# LNA.net
KiCad netlist of a schematic drawn in Altium Designer
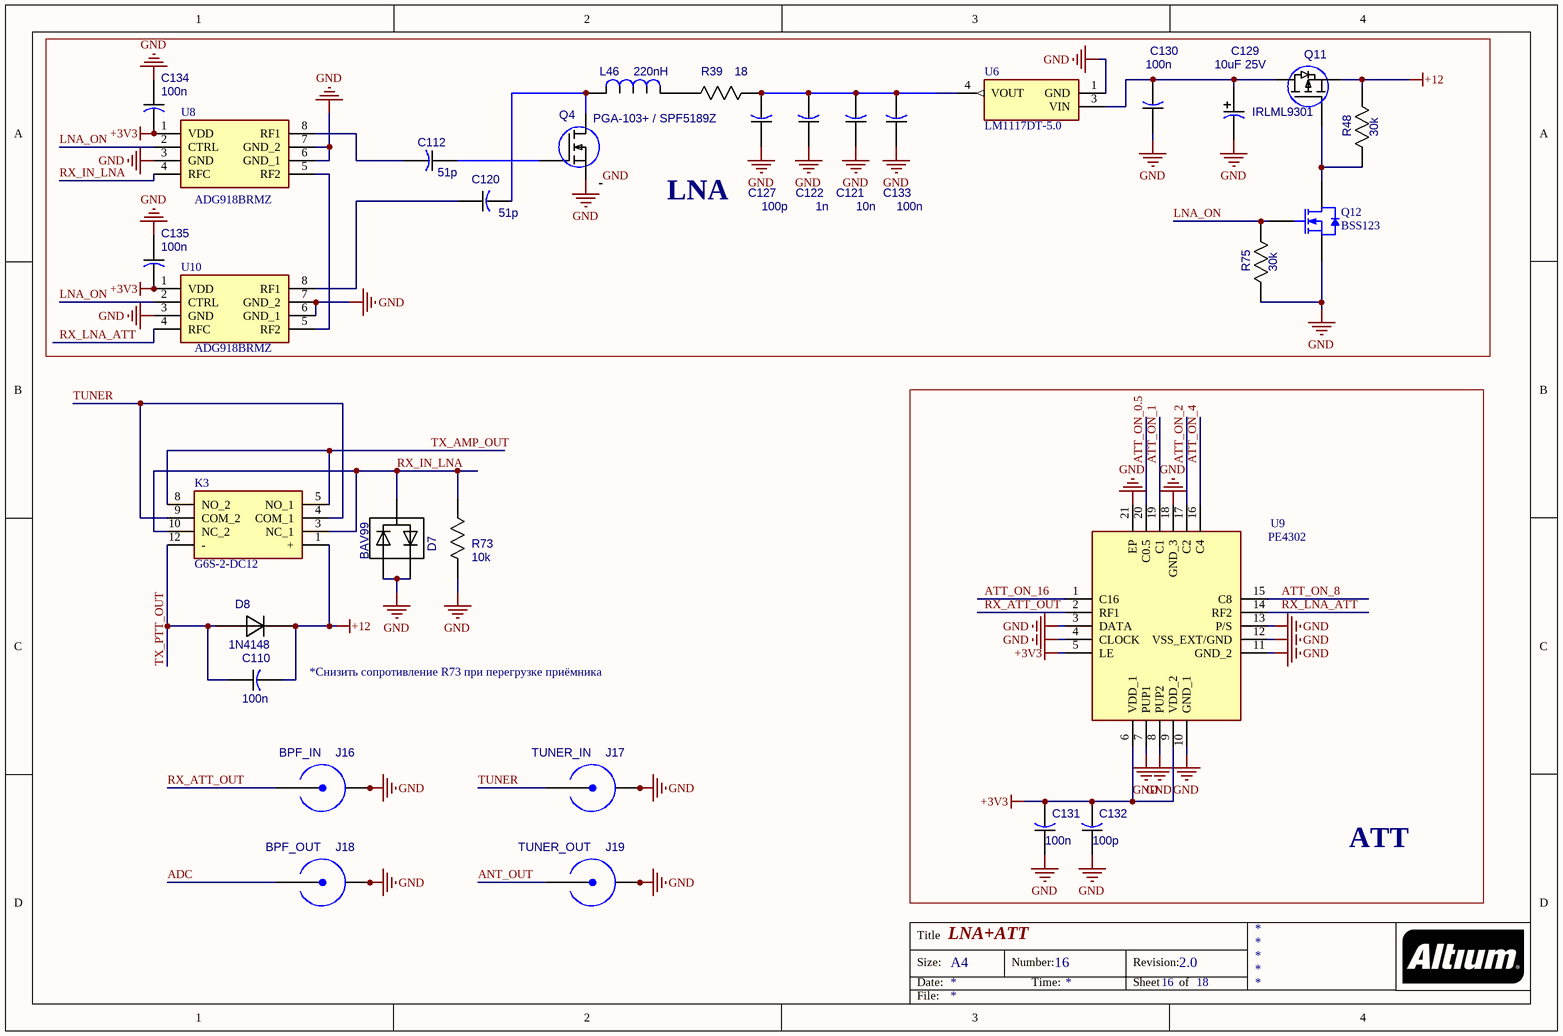
[diagram p0: LNA.SchDoc]

(export (version "E")
  (design (tool "Eeschema 10.0.6"))
  (components
    (comp (ref "C110")
      (value "100n")
      (footprint "CAP_0805")
      (description "CAP_0805")
      (libsource (lib "*") (part "CAP_0805"))
    )
    (comp (ref "C112")
      (value "51p")
      (footprint "CAP_0805")
      (description "CAP_0805")
      (libsource (lib "*") (part "CAP_0805"))
    )
    (comp (ref "C120")
      (value "51p")
      (footprint "CAP_0805")
      (description "CAP_0805")
      (libsource (lib "*") (part "CAP_0805"))
    )
    (comp (ref "C121")
      (value "10n")
      (footprint "6-0805_M")
      (description "CAP_0805")
      (libsource (lib "*") (part "CAP_0805"))
    )
    (comp (ref "C122")
      (value "1n")
      (footprint "6-0805_M")
      (description "CAP_0805")
      (libsource (lib "*") (part "CAP_0805"))
    )
    (comp (ref "C127")
      (value "100p")
      (footprint "6-0805_M")
      (description "CAP_0805")
      (libsource (lib "*") (part "CAP_0805"))
    )
    (comp (ref "C129")
      (value "10uF 25V")
      (footprint "CAPAE_5.3x5.3h6.1")
      (description "CAPAE_5.3x5.3h6.1")
      (libsource (lib "*") (part "CAPAE_5.3x5.3h6.1"))
    )
    (comp (ref "C130")
      (value "100n")
      (footprint "CAP_0805")
      (description "CAP_0805")
      (libsource (lib "") (part "CAP_0805_1"))
    )
    (comp (ref "C131")
      (value "100n")
      (footprint "6-0805_M")
      (description "CAP_0805")
      (libsource (lib "*") (part "CAP_0805"))
    )
    (comp (ref "C132")
      (value "100p")
      (footprint "6-0805_M")
      (description "CAP_0805")
      (libsource (lib "*") (part "CAP_0805"))
    )
    (comp (ref "C133")
      (value "100n")
      (footprint "CAP_0805")
      (description "CAP_0805")
      (libsource (lib "*") (part "CAP_0805"))
    )
    (comp (ref "C134")
      (value "100n")
      (footprint "CAP_0805")
      (description "CAP_0805")
      (libsource (lib "*") (part "CAP_0805"))
    )
    (comp (ref "C135")
      (value "100n")
      (footprint "CAP_0805")
      (description "CAP_0805")
      (libsource (lib "*") (part "CAP_0805"))
    )
    (comp (ref "D7") (value "BAV99") (footprint "SOT23") (libsource (lib "*") (part "BAV99")))
    (comp (ref "D8") (value "1N4148") (footprint "SS14") (libsource (lib "RF-UNIT-BIG") (part "1N4148")))
    (comp (ref "J16")
      (value "BPF_IN")
      (footprint "31-5431")
      (description "SMA")
      (libsource (lib "RF-UNIT_1") (part "31-5431"))
    )
    (comp (ref "J17")
      (value "TUNER_IN")
      (footprint "31-5431")
      (description "SMA")
      (libsource (lib "RF-UNIT_1") (part "31-5431"))
    )
    (comp (ref "J18")
      (value "BPF_OUT")
      (footprint "31-5431")
      (description "SMA")
      (libsource (lib "RF-UNIT_1") (part "31-5431"))
    )
    (comp (ref "J19")
      (value "TUNER_OUT")
      (footprint "31-5431")
      (description "SMA")
      (libsource (lib "RF-UNIT_1") (part "31-5431"))
    )
    (comp (ref "K3")
      (value "G6S-2-DC12")
      (footprint "G6S2DC12")
      (description "Relay or Contactor")
      (fields (field (name "MOUSER PART NUMBER") "653-G6S-2-DC12A"))
      (libsource (lib "*") (part "G6S-2-DC12"))
    )
    (comp (ref "L46")
      (value "220nH")
      (footprint "IND_1206")
      (description "IND_1206")
      (libsource (lib "*") (part "IND_1206"))
    )
    (comp (ref "Q4")
      (value "PGA-103+ / SPF5189Z")
      (footprint "SOT89")
      (libsource (lib "*") (part "PGA-103+"))
    )
    (comp (ref "Q11")
      (value "IRLML9301")
      (footprint "SOT23")
      (description "MOSFET")
      (libsource (lib "*") (part "MOSFET_ENH_PD"))
    )
    (comp (ref "Q12")
      (value "BSS123")
      (footprint "FAIR-SOT23-3_V")
      (fields (field (name "MANUFACTURER") "Fairchild"))
      (libsource (lib "Altium Content Vault") (part "NEMOS-GSD-3"))
    )
    (comp (ref "R39")
      (value "18")
      (footprint "RES_1206")
      (description "RES_1206")
      (libsource (lib "*") (part "RES_1206"))
    )
    (comp (ref "R48")
      (value "30k")
      (footprint "RES_0805")
      (description "RES_0805")
      (libsource (lib "*") (part "RES_0805"))
    )
    (comp (ref "R73")
      (value "10k")
      (footprint "RES_1206")
      (description "RES_1206")
      (libsource (lib "*") (part "RES_1206"))
    )
    (comp (ref "R75")
      (value "30k")
      (footprint "RES_0805")
      (description "RES_0805")
      (libsource (lib "*") (part "RES_0805"))
    )
    (comp (ref "U6")
      (value "LM1117DT-5.0")
      (footprint "SamacSys:TO228P991X238-3N")
      (description "Integrated Circuit")
      (fields
        (field (name "MANUFACTURER_PART_NUMBER") "LM1117DT-ADJ")
        (field (name "MOUSER PART NUMBER") "926-LM1117DT-ADJ")
      )
      (libsource (lib "*") (part "LM1117DT-ADJ"))
    )
    (comp (ref "U8")
      (value "ADG918BRMZ")
      (footprint "SOP65P490X110-8N")
      (description "Integrated Circuit")
      (fields (field (name "MOUSER PART NUMBER") "584-ADG918BRMZ") (field (name "RS PART NUMBER") "4969212P"))
      (libsource (lib "RF-UNIT-BIG") (part "ADG918BRMZ"))
    )
    (comp (ref "U9")
      (value "PE4302")
      (footprint "QFN50P400X400X90-21N")
      (description "Integrated Circuit")
      (fields (field (name "MANUFACTURER_PART_NUMBER") "PE4312C-Z"))
      (libsource (lib "RF-UNIT-BIG") (part "PE4312C-Z"))
    )
    (comp (ref "U10")
      (value "ADG918BRMZ")
      (footprint "SOP65P490X110-8N")
      (description "Integrated Circuit")
      (fields (field (name "MOUSER PART NUMBER") "584-ADG918BRMZ") (field (name "RS PART NUMBER") "4969212P"))
      (libsource (lib "RF-UNIT-BIG") (part "ADG918BRMZ"))
    )
  )
  (nets
    (net (code "1") (name "+3V3") (class "Default")
      (node (ref "C131") (pin "2") (pinfunction "2_2") (pintype "passive"))
      (node (ref "C132") (pin "2") (pinfunction "2_2") (pintype "passive"))
      (node (ref "C134") (pin "2") (pinfunction "2_2") (pintype "passive"))
      (node (ref "C135") (pin "2") (pinfunction "2_2") (pintype "passive"))
      (node (ref "U10") (pin "1") (pinfunction "VDD_1") (pintype "power_in"))
      (node (ref "U8") (pin "1") (pinfunction "VDD_1") (pintype "power_in"))
      (node (ref "U9") (pin "5") (pinfunction "LE_5") (pintype "passive"))
      (node (ref "U9") (pin "6") (pinfunction "VDD_1_6") (pintype "passive"))
      (node (ref "U9") (pin "9") (pinfunction "VDD_2_9") (pintype "passive"))
    )
    (net (code "2") (name "+12") (class "Default")
      (node (ref "C110") (pin "2") (pinfunction "2_2") (pintype "passive"))
      (node (ref "D8") (pin "1") (pinfunction "K_1") (pintype "passive"))
      (node (ref "K3") (pin "1") (pinfunction "+_1") (pintype "passive"))
      (node (ref "Q11") (pin "2") (pinfunction "S_2") (pintype "passive"))
      (node (ref "R48") (pin "2") (pinfunction "2_2") (pintype "passive"))
    )
    (net (code "3") (name "/ADC") (class "Default")
      (node (ref "J18") (pin "5") (pinfunction "CON_5") (pintype "passive"))
    )
    (net (code "4") (name "/ANT_OUT") (class "Default")
      (node (ref "J19") (pin "5") (pinfunction "CON_5") (pintype "passive"))
    )
    (net (code "5") (name "/ATT_ON_0.5") (class "Default")
      (node (ref "U9") (pin "20") (pinfunction "C0.5_20") (pintype "passive"))
    )
    (net (code "6") (name "/ATT_ON_1") (class "Default")
      (node (ref "U9") (pin "19") (pinfunction "C1_19") (pintype "passive"))
    )
    (net (code "7") (name "/ATT_ON_2") (class "Default")
      (node (ref "U9") (pin "17") (pinfunction "C2_17") (pintype "passive"))
    )
    (net (code "8") (name "/ATT_ON_4") (class "Default")
      (node (ref "U9") (pin "16") (pinfunction "C4_16") (pintype "passive"))
    )
    (net (code "9") (name "/ATT_ON_8") (class "Default")
      (node (ref "U9") (pin "15") (pinfunction "C8_15") (pintype "passive"))
    )
    (net (code "10") (name "/ATT_ON_16") (class "Default")
      (node (ref "U9") (pin "1") (pinfunction "C16_1") (pintype "passive"))
    )
    (net (code "11") (name "/LNA_ON") (class "Default")
      (node (ref "Q12") (pin "1") (pinfunction "G_1") (pintype "passive"))
      (node (ref "R75") (pin "2") (pinfunction "2_2") (pintype "passive"))
      (node (ref "U10") (pin "2") (pinfunction "CTRL_2") (pintype "passive"))
      (node (ref "U8") (pin "2") (pinfunction "CTRL_2") (pintype "passive"))
    )
    (net (code "12") (name "/RX_ATT_OUT") (class "Default")
      (node (ref "J16") (pin "5") (pinfunction "CON_5") (pintype "passive"))
      (node (ref "U9") (pin "2") (pinfunction "RF1_2") (pintype "passive"))
    )
    (net (code "13") (name "/RX_IN_LNA") (class "Default")
      (node (ref "D7") (pin "3") (pinfunction "C(D1),A(D2)_3") (pintype "passive"))
      (node (ref "K3") (pin "10") (pinfunction "NC_2_10") (pintype "passive"))
      (node (ref "K3") (pin "3") (pinfunction "NC_1_3") (pintype "passive"))
      (node (ref "R73") (pin "2") (pinfunction "2_2") (pintype "passive"))
      (node (ref "U8") (pin "4") (pinfunction "RFC_4") (pintype "passive"))
    )
    (net (code "14") (name "/RX_LNA_ATT") (class "Default")
      (node (ref "U10") (pin "4") (pinfunction "RFC_4") (pintype "passive"))
      (node (ref "U9") (pin "14") (pinfunction "RF2_14") (pintype "passive"))
    )
    (net (code "15") (name "/TUNER") (class "Default")
      (node (ref "J17") (pin "5") (pinfunction "CON_5") (pintype "passive"))
      (node (ref "K3") (pin "4") (pinfunction "COM_1_4") (pintype "passive"))
      (node (ref "K3") (pin "9") (pinfunction "COM_2_9") (pintype "passive"))
    )
    (net (code "16") (name "/TX_AMP_OUT") (class "Default")
      (node (ref "K3") (pin "5") (pinfunction "NO_1_5") (pintype "passive"))
      (node (ref "K3") (pin "8") (pinfunction "NO_2_8") (pintype "passive"))
    )
    (net (code "17") (name "/TX_PTT_OUT") (class "Default")
      (node (ref "C110") (pin "1") (pinfunction "1_1") (pintype "passive"))
      (node (ref "D8") (pin "2") (pinfunction "A_2") (pintype "passive"))
      (node (ref "K3") (pin "12") (pinfunction "-_12") (pintype "passive"))
    )
    (net (code "18") (name "GND") (class "Default")
      (node (ref "C121") (pin "1") (pinfunction "1_1") (pintype "passive"))
      (node (ref "C122") (pin "1") (pinfunction "1_1") (pintype "passive"))
      (node (ref "C127") (pin "1") (pinfunction "1_1") (pintype "passive"))
      (node (ref "C129") (pin "2") (pinfunction "MINUS_2") (pintype "passive"))
      (node (ref "C130") (pin "1") (pinfunction "1_1") (pintype "passive"))
      (node (ref "C131") (pin "1") (pinfunction "1_1") (pintype "passive"))
      (node (ref "C132") (pin "1") (pinfunction "1_1") (pintype "passive"))
      (node (ref "C133") (pin "1") (pinfunction "1_1") (pintype "passive"))
      (node (ref "C134") (pin "1") (pinfunction "1_1") (pintype "passive"))
      (node (ref "C135") (pin "1") (pinfunction "1_1") (pintype "passive"))
      (node (ref "D7") (pin "1") (pinfunction "A(D1)_1") (pintype "passive"))
      (node (ref "D7") (pin "2") (pinfunction "C(D2)_2") (pintype "passive"))
      (node (ref "J16") (pin "1") (pinfunction "GND_1") (pintype "passive"))
      (node (ref "J16") (pin "2") (pinfunction "GND_2") (pintype "passive"))
      (node (ref "J16") (pin "3") (pinfunction "GND_3") (pintype "passive"))
      (node (ref "J16") (pin "4") (pinfunction "GND_4") (pintype "passive"))
      (node (ref "J17") (pin "1") (pinfunction "GND_1") (pintype "passive"))
      (node (ref "J17") (pin "2") (pinfunction "GND_2") (pintype "passive"))
      (node (ref "J17") (pin "3") (pinfunction "GND_3") (pintype "passive"))
      (node (ref "J17") (pin "4") (pinfunction "GND_4") (pintype "passive"))
      (node (ref "J18") (pin "1") (pinfunction "GND_1") (pintype "passive"))
      (node (ref "J18") (pin "2") (pinfunction "GND_2") (pintype "passive"))
      (node (ref "J18") (pin "3") (pinfunction "GND_3") (pintype "passive"))
      (node (ref "J18") (pin "4") (pinfunction "GND_4") (pintype "passive"))
      (node (ref "J19") (pin "1") (pinfunction "GND_1") (pintype "passive"))
      (node (ref "J19") (pin "2") (pinfunction "GND_2") (pintype "passive"))
      (node (ref "J19") (pin "3") (pinfunction "GND_3") (pintype "passive"))
      (node (ref "J19") (pin "4") (pinfunction "GND_4") (pintype "passive"))
      (node (ref "Q12") (pin "2") (pinfunction "S_2") (pintype "passive"))
      (node (ref "Q4") (pin "0") (pinfunction "0_0") (pintype "passive"))
      (node (ref "Q4") (pin "2") (pinfunction "S_2") (pintype "passive"))
      (node (ref "R73") (pin "1") (pinfunction "1_1") (pintype "passive"))
      (node (ref "R75") (pin "1") (pinfunction "1_1") (pintype "passive"))
      (node (ref "U10") (pin "3") (pinfunction "GND_3") (pintype "power_in"))
      (node (ref "U10") (pin "6") (pinfunction "GND_1_6") (pintype "power_in"))
      (node (ref "U10") (pin "7") (pinfunction "GND_2_7") (pintype "power_in"))
      (node (ref "U6") (pin "1") (pinfunction "GND_1") (pintype "passive"))
      (node (ref "U8") (pin "3") (pinfunction "GND_3") (pintype "power_in"))
      (node (ref "U8") (pin "6") (pinfunction "GND_1_6") (pintype "power_in"))
      (node (ref "U8") (pin "7") (pinfunction "GND_2_7") (pintype "power_in"))
      (node (ref "U9") (pin "10") (pinfunction "GND_1_10") (pintype "passive"))
      (node (ref "U9") (pin "11") (pinfunction "GND_2_11") (pintype "passive"))
      (node (ref "U9") (pin "12") (pinfunction "VSS_EXT/GND_12") (pintype "passive"))
      (node (ref "U9") (pin "13") (pinfunction "P/S_13") (pintype "passive"))
      (node (ref "U9") (pin "18") (pinfunction "GND_3_18") (pintype "passive"))
      (node (ref "U9") (pin "21") (pinfunction "EP_21") (pintype "passive"))
      (node (ref "U9") (pin "3") (pinfunction "DATA_3") (pintype "passive"))
      (node (ref "U9") (pin "4") (pinfunction "CLOCK_4") (pintype "passive"))
      (node (ref "U9") (pin "7") (pinfunction "PUP1_7") (pintype "passive"))
      (node (ref "U9") (pin "8") (pinfunction "PUP2_8") (pintype "passive"))
    )
    (net (code "19") (name "Net-(C129-PLUS)") (class "Default")
      (node (ref "C129") (pin "1") (pinfunction "PLUS_1") (pintype "passive"))
      (node (ref "C130") (pin "2") (pinfunction "2_2") (pintype "passive"))
      (node (ref "Q11") (pin "3") (pinfunction "D_3") (pintype "passive"))
      (node (ref "U6") (pin "3") (pinfunction "VIN_3") (pintype "passive"))
    )
    (net (code "20") (name "Net-(L46-1)") (class "Default")
      (node (ref "C120") (pin "2") (pinfunction "2_2") (pintype "passive"))
      (node (ref "L46") (pin "2") (pinfunction "1_2") (pintype "passive"))
      (node (ref "Q4") (pin "3") (pinfunction "D_3") (pintype "passive"))
    )
    (net (code "21") (name "Net-(L46-2)") (class "Default")
      (node (ref "L46") (pin "1") (pinfunction "2_1") (pintype "passive"))
      (node (ref "R39") (pin "2") (pinfunction "2_2") (pintype "passive"))
    )
    (net (code "22") (name "Net-(Q4-G)") (class "Default")
      (node (ref "C112") (pin "1") (pinfunction "1_1") (pintype "passive"))
      (node (ref "Q4") (pin "1") (pinfunction "G_1") (pintype "passive"))
    )
    (net (code "23") (name "Net-(Q11-G)") (class "Default")
      (node (ref "Q11") (pin "1") (pinfunction "G_1") (pintype "passive"))
      (node (ref "Q12") (pin "3") (pinfunction "D_3") (pintype "passive"))
      (node (ref "R48") (pin "1") (pinfunction "1_1") (pintype "passive"))
    )
    (net (code "24") (name "Net-(U6-VOUT)") (class "Default")
      (node (ref "C121") (pin "2") (pinfunction "2_2") (pintype "passive"))
      (node (ref "C122") (pin "2") (pinfunction "2_2") (pintype "passive"))
      (node (ref "C127") (pin "2") (pinfunction "2_2") (pintype "passive"))
      (node (ref "C133") (pin "2") (pinfunction "2_2") (pintype "passive"))
      (node (ref "R39") (pin "1") (pinfunction "1_1") (pintype "passive"))
      (node (ref "U6") (pin "4") (pinfunction "VOUT_4") (pintype "output"))
    )
    (net (code "25") (name "Net-(U8-RF1)") (class "Default")
      (node (ref "C112") (pin "2") (pinfunction "2_2") (pintype "passive"))
      (node (ref "U8") (pin "8") (pinfunction "RF1_8") (pintype "passive"))
    )
    (net (code "26") (name "Net-(U10-RF1)") (class "Default")
      (node (ref "C120") (pin "1") (pinfunction "1_1") (pintype "passive"))
      (node (ref "U10") (pin "8") (pinfunction "RF1_8") (pintype "passive"))
    )
    (net (code "27") (name "Net-(U10-RF2)") (class "Default")
      (node (ref "U10") (pin "5") (pinfunction "RF2_5") (pintype "passive"))
      (node (ref "U8") (pin "5") (pinfunction "RF2_5") (pintype "passive"))
    )
  )
)
